# Sheet1.net
KiCad netlist of a schematic drawn in Altium Designer
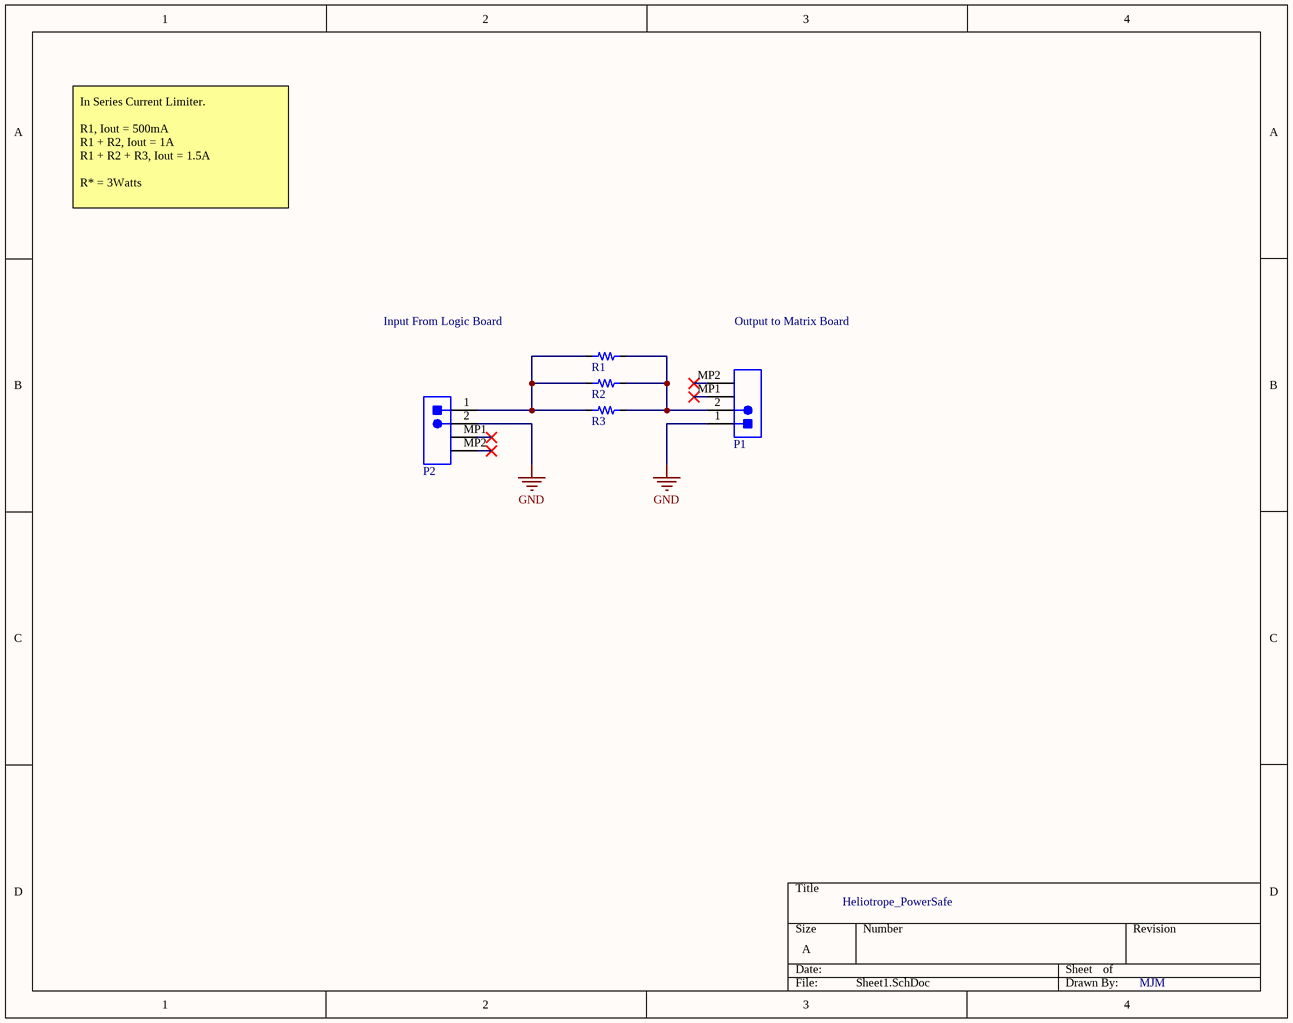
[diagram p0: Sheet1.SchDoc]

(export (version "E")
  (design (tool "Eeschema 10.0.6"))
  (components
    (comp (ref "P1")
      (value "53261-0271")
      (footprint "MOLX-53261-0271_V")
      (description "1.25mm Pitch PicoBlade™ Header, Surface Mount, Right Angle, Lead-Free, 2 Circuits")
      (libsource (lib "") (part "CN-1P-2M-R2_1"))
    )
    (comp (ref "P2")
      (value "53261-0271")
      (footprint "MOLX-53261-0271_V")
      (description "1.25mm Pitch PicoBlade™ Header, Surface Mount, Right Angle, Lead-Free, 2 Circuits")
      (libsource (lib "Microcom Corporation") (part "CN-1P-2M-R2"))
    )
    (comp (ref "R1")
      (value "352210RFT")
      (footprint "RESC6331X70N")
      (description "Res Thick Film 2512 10 Ohm 1% 3W ±100ppm/C Pad SMD T/R")
      (libsource (lib "Microcom Corporation") (part "2176231-1"))
    )
    (comp (ref "R2")
      (value "352210RFT")
      (footprint "RESC6331X70N")
      (description "Res Thick Film 2512 10 Ohm 1% 3W ±100ppm/C Pad SMD T/R")
      (libsource (lib "Microcom Corporation") (part "2176231-1"))
    )
    (comp (ref "R3")
      (value "352210RFT")
      (footprint "RESC6331X70N")
      (description "Res Thick Film 2512 10 Ohm 1% 3W ±100ppm/C Pad SMD T/R")
      (libsource (lib "Microcom Corporation") (part "2176231-1"))
    )
  )
  (nets
    (net (code "1") (name "GND") (class "Default")
      (node (ref "P1") (pin "1") (pinfunction "1_1") (pintype "passive"))
      (node (ref "P2") (pin "2") (pinfunction "2_2") (pintype "passive"))
    )
    (net (code "2") (name "Net-(P1-Pad2)") (class "Default")
      (node (ref "P1") (pin "2") (pinfunction "2_2") (pintype "passive"))
      (node (ref "R1") (pin "2") (pinfunction "2_2") (pintype "passive"))
      (node (ref "R2") (pin "2") (pinfunction "2_2") (pintype "passive"))
      (node (ref "R3") (pin "2") (pinfunction "2_2") (pintype "passive"))
    )
    (net (code "3") (name "Net-(P2-Pad1)") (class "Default")
      (node (ref "P2") (pin "1") (pinfunction "1_1") (pintype "passive"))
      (node (ref "R1") (pin "1") (pinfunction "1_1") (pintype "passive"))
      (node (ref "R2") (pin "1") (pinfunction "1_1") (pintype "passive"))
      (node (ref "R3") (pin "1") (pinfunction "1_1") (pintype "passive"))
    )
    (net (code "4") (name "unconnected-(P1-PadMP1)") (class "Default")
      (node (ref "P1") (pin "MP1") (pinfunction "MP1_MP1") (pintype "passive+no_connect"))
    )
    (net (code "5") (name "unconnected-(P1-PadMP2)") (class "Default")
      (node (ref "P1") (pin "MP2") (pinfunction "MP2_MP2") (pintype "passive+no_connect"))
    )
    (net (code "6") (name "unconnected-(P2-PadMP1)") (class "Default")
      (node (ref "P2") (pin "MP1") (pinfunction "MP1_MP1") (pintype "passive+no_connect"))
    )
    (net (code "7") (name "unconnected-(P2-PadMP2)") (class "Default")
      (node (ref "P2") (pin "MP2") (pinfunction "MP2_MP2") (pintype "passive+no_connect"))
    )
  )
)
